# 08-DEV_POWER.net
KiCad netlist of a schematic drawn in Altium Designer
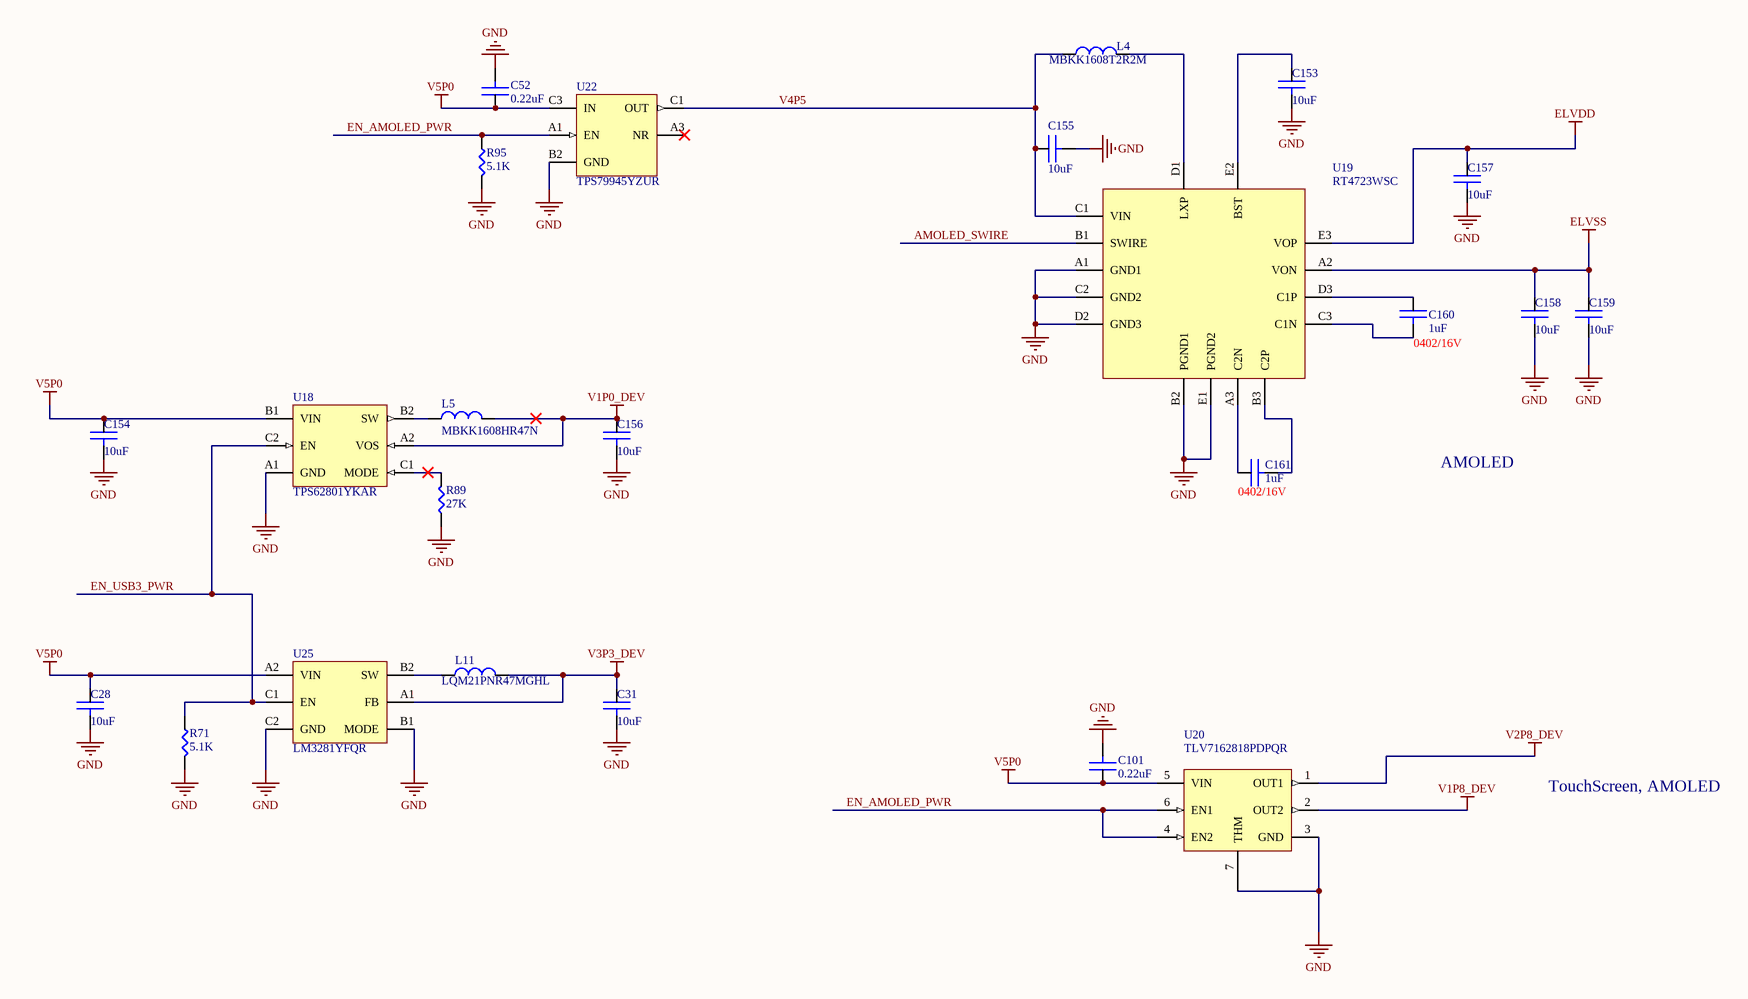
[diagram p0: 08-DEV_POWER.SchDoc]

(export (version "E")
  (design (tool "Eeschema 10.0.6"))
  (components
    (comp (ref "C28") (value "10uF") (footprint "C0402") (libsource (lib "AMOLED") (part "10uF/0402")))
    (comp (ref "C31") (value "10uF") (footprint "C0402") (libsource (lib "AMOLED") (part "10uF/0402")))
    (comp (ref "C52") (value "0.22uF") (footprint "C0201") (libsource (lib "AMOLED") (part "0.22uF/0201")))
    (comp (ref "C101") (value "0.22uF") (footprint "C0201") (libsource (lib "AMOLED") (part "0.22uF/0201")))
    (comp (ref "C153") (value "10uF") (footprint "C0402") (libsource (lib "AMOLED") (part "10uF/0402")))
    (comp (ref "C154") (value "10uF") (footprint "C0402") (libsource (lib "AMOLED") (part "10uF/0402")))
    (comp (ref "C155") (value "10uF") (footprint "C0402") (libsource (lib "AMOLED") (part "10uF/0402")))
    (comp (ref "C156") (value "10uF") (footprint "C0402") (libsource (lib "AMOLED") (part "10uF/0402")))
    (comp (ref "C157") (value "10uF") (footprint "C0402") (libsource (lib "AMOLED") (part "10uF/0402")))
    (comp (ref "C158") (value "10uF") (footprint "C0402") (libsource (lib "AMOLED") (part "10uF/0402")))
    (comp (ref "C159") (value "10uF") (footprint "C0402") (libsource (lib "AMOLED") (part "10uF/0402")))
    (comp (ref "C160") (value "1uF") (footprint "C0402") (libsource (lib "AMOLED") (part "1uF/0402/16V")))
    (comp (ref "C161") (value "1uF") (footprint "C0402") (libsource (lib "AMOLED") (part "1uF/0402/16V")))
    (comp (ref "L4")
      (value "MBKK1608T2R2M")
      (footprint "L0603")
      (libsource (lib "AMOLED") (part "2.2uH/MBKK1608T2R2M"))
    )
    (comp (ref "L5")
      (value "MBKK1608HR47N")
      (footprint "L0603")
      (libsource (lib "AMOLED") (part "0.47uH/MBKK1608HR47N"))
    )
    (comp (ref "L11")
      (value "LQM21PNR47MGHL")
      (footprint "L0805")
      (libsource (lib "AMOLED") (part "0.47uH/LQM21PNR47MGHL"))
    )
    (comp (ref "R71")
      (value "5.1K")
      (footprint "R0201")
      (libsource (lib "Control_Board") (part "5.1K/1%/0201"))
    )
    (comp (ref "R89")
      (value "27K")
      (footprint "R0201")
      (libsource (lib "Control_Board") (part "27K/1%/0201"))
    )
    (comp (ref "R95")
      (value "5.1K")
      (footprint "R0201")
      (libsource (lib "Control_Board") (part "5.1K/1%/0201"))
    )
    (comp (ref "U18")
      (value "TPS62801YKAR")
      (footprint "DSBGA6")
      (description "IC REG BCK 0.85-1.5V 1.0A")
      (libsource (lib "PSD_V2_Schlib") (part "TPS62801YKAR"))
    )
    (comp (ref "U19")
      (value "RT4723WSC")
      (footprint "WLCSP-15B")
      (libsource (lib "AMOLED") (part "RT4723WSC"))
    )
    (comp (ref "U20")
      (value "TLV7162818PDPQR")
      (footprint "X2SON-6")
      (description "Dual LDO 1.8V, 2.8V X2SON-6")
      (libsource (lib "PSD_V2_Schlib") (part "TLV7162818PDPQR"))
    )
    (comp (ref "U22")
      (value "TPS79945YZUR")
      (footprint "DSBGA5")
      (description "LDO 200mA DSBGA")
      (libsource (lib "PSD_V2_Schlib") (part "TPS79945YZUR"))
    )
    (comp (ref "U25")
      (value "LM3281YFQR")
      (footprint "DSBGA6")
      (libsource (lib "AMOLED") (part "LM3281YFQR"))
    )
  )
  (nets
    (net (code "1") (name "/AMOLED_SWIRE") (class "Default")
      (node (ref "U19") (pin "B1") (pinfunction "SWIRE_B1") (pintype "passive"))
    )
    (net (code "2") (name "/EN_AMOLED_PWR") (class "Default")
      (node (ref "R95") (pin "1") (pinfunction "1_1") (pintype "passive"))
      (node (ref "U20") (pin "4") (pinfunction "EN2_4") (pintype "input"))
      (node (ref "U20") (pin "6") (pinfunction "EN1_6") (pintype "input"))
      (node (ref "U22") (pin "A1") (pinfunction "EN_A1") (pintype "input"))
    )
    (net (code "3") (name "/EN_USB3_PWR") (class "Default")
      (node (ref "R71") (pin "1") (pinfunction "1_1") (pintype "passive"))
      (node (ref "U18") (pin "C2") (pinfunction "EN_C2") (pintype "input"))
      (node (ref "U25") (pin "C1") (pinfunction "EN_C1") (pintype "passive"))
    )
    (net (code "4") (name "/V4P5") (class "Default")
      (node (ref "C155") (pin "1") (pinfunction "1_1") (pintype "passive"))
      (node (ref "L4") (pin "1") (pinfunction "1_1") (pintype "passive"))
      (node (ref "U19") (pin "C1") (pinfunction "VIN_C1") (pintype "passive"))
      (node (ref "U22") (pin "C1") (pinfunction "OUT_C1") (pintype "output"))
    )
    (net (code "5") (name "ELVDD") (class "Default")
      (node (ref "C157") (pin "1") (pinfunction "1_1") (pintype "passive"))
      (node (ref "U19") (pin "E3") (pinfunction "VOP_E3") (pintype "passive"))
    )
    (net (code "6") (name "ELVSS") (class "Default")
      (node (ref "C158") (pin "1") (pinfunction "1_1") (pintype "passive"))
      (node (ref "C159") (pin "1") (pinfunction "1_1") (pintype "passive"))
      (node (ref "U19") (pin "A2") (pinfunction "VON_A2") (pintype "passive"))
    )
    (net (code "7") (name "GND") (class "Default")
      (node (ref "C101") (pin "2") (pinfunction "2_2") (pintype "passive"))
      (node (ref "C153") (pin "2") (pinfunction "2_2") (pintype "passive"))
      (node (ref "C154") (pin "2") (pinfunction "2_2") (pintype "passive"))
      (node (ref "C155") (pin "2") (pinfunction "2_2") (pintype "passive"))
      (node (ref "C156") (pin "2") (pinfunction "2_2") (pintype "passive"))
      (node (ref "C157") (pin "2") (pinfunction "2_2") (pintype "passive"))
      (node (ref "C158") (pin "2") (pinfunction "2_2") (pintype "passive"))
      (node (ref "C159") (pin "2") (pinfunction "2_2") (pintype "passive"))
      (node (ref "C28") (pin "2") (pinfunction "2_2") (pintype "passive"))
      (node (ref "C31") (pin "2") (pinfunction "2_2") (pintype "passive"))
      (node (ref "C52") (pin "2") (pinfunction "2_2") (pintype "passive"))
      (node (ref "R71") (pin "2") (pinfunction "2_2") (pintype "passive"))
      (node (ref "R89") (pin "1") (pinfunction "1_1") (pintype "passive"))
      (node (ref "R95") (pin "2") (pinfunction "2_2") (pintype "passive"))
      (node (ref "U18") (pin "A1") (pinfunction "GND_A1") (pintype "power_in"))
      (node (ref "U19") (pin "A1") (pinfunction "GND1_A1") (pintype "passive"))
      (node (ref "U19") (pin "B2") (pinfunction "PGND1_B2") (pintype "passive"))
      (node (ref "U19") (pin "C2") (pinfunction "GND2_C2") (pintype "passive"))
      (node (ref "U19") (pin "D2") (pinfunction "GND3_D2") (pintype "passive"))
      (node (ref "U19") (pin "E1") (pinfunction "PGND2_E1") (pintype "passive"))
      (node (ref "U20") (pin "3") (pinfunction "GND_3") (pintype "passive"))
      (node (ref "U20") (pin "7") (pinfunction "THM_7") (pintype "passive"))
      (node (ref "U22") (pin "B2") (pinfunction "GND_B2") (pintype "power_in"))
      (node (ref "U25") (pin "B1") (pinfunction "MODE_B1") (pintype "passive"))
      (node (ref "U25") (pin "C2") (pinfunction "GND_C2") (pintype "passive"))
    )
    (net (code "8") (name "Net-(U18-MODE)") (class "Default")
      (node (ref "R89") (pin "2") (pinfunction "2_2") (pintype "passive"))
      (node (ref "U18") (pin "C1") (pinfunction "MODE_C1") (pintype "input"))
    )
    (net (code "9") (name "Net-(U18-SW)") (class "Default")
      (node (ref "L5") (pin "1") (pinfunction "1_1") (pintype "passive"))
      (node (ref "U18") (pin "B2") (pinfunction "SW_B2") (pintype "output"))
    )
    (net (code "10") (name "Net-(U19-BST)") (class "Default")
      (node (ref "C153") (pin "1") (pinfunction "1_1") (pintype "passive"))
      (node (ref "U19") (pin "E2") (pinfunction "BST_E2") (pintype "passive"))
    )
    (net (code "11") (name "Net-(U19-C1N)") (class "Default")
      (node (ref "C160") (pin "2") (pinfunction "2_2") (pintype "passive"))
      (node (ref "U19") (pin "C3") (pinfunction "C1N_C3") (pintype "passive"))
    )
    (net (code "12") (name "Net-(U19-C1P)") (class "Default")
      (node (ref "C160") (pin "1") (pinfunction "1_1") (pintype "passive"))
      (node (ref "U19") (pin "D3") (pinfunction "C1P_D3") (pintype "passive"))
    )
    (net (code "13") (name "Net-(U19-C2N)") (class "Default")
      (node (ref "C161") (pin "1") (pinfunction "1_1") (pintype "passive"))
      (node (ref "U19") (pin "A3") (pinfunction "C2N_A3") (pintype "passive"))
    )
    (net (code "14") (name "Net-(U19-C2P)") (class "Default")
      (node (ref "C161") (pin "2") (pinfunction "2_2") (pintype "passive"))
      (node (ref "U19") (pin "B3") (pinfunction "C2P_B3") (pintype "passive"))
    )
    (net (code "15") (name "Net-(U19-LXP)") (class "Default")
      (node (ref "L4") (pin "2") (pinfunction "2_2") (pintype "passive"))
      (node (ref "U19") (pin "D1") (pinfunction "LXP_D1") (pintype "passive"))
    )
    (net (code "16") (name "Net-(U25-SW)") (class "Default")
      (node (ref "L11") (pin "1") (pinfunction "1_1") (pintype "passive"))
      (node (ref "U25") (pin "B2") (pinfunction "SW_B2") (pintype "passive"))
    )
    (net (code "17") (name "V1P0_DEV") (class "Default")
      (node (ref "C156") (pin "1") (pinfunction "1_1") (pintype "passive"))
      (node (ref "L5") (pin "2") (pinfunction "2_2") (pintype "passive"))
      (node (ref "U18") (pin "A2") (pinfunction "VOS_A2") (pintype "input"))
    )
    (net (code "18") (name "V1P8_DEV") (class "Default")
      (node (ref "U20") (pin "2") (pinfunction "OUT2_2") (pintype "output"))
    )
    (net (code "19") (name "V2P8_DEV") (class "Default")
      (node (ref "U20") (pin "1") (pinfunction "OUT1_1") (pintype "output"))
    )
    (net (code "20") (name "V3P3_DEV") (class "Default")
      (node (ref "C31") (pin "1") (pinfunction "1_1") (pintype "passive"))
      (node (ref "L11") (pin "2") (pinfunction "2_2") (pintype "passive"))
      (node (ref "U25") (pin "A1") (pinfunction "FB_A1") (pintype "passive"))
    )
    (net (code "21") (name "V5P0") (class "Default")
      (node (ref "C101") (pin "1") (pinfunction "1_1") (pintype "passive"))
      (node (ref "C154") (pin "1") (pinfunction "1_1") (pintype "passive"))
      (node (ref "C28") (pin "1") (pinfunction "1_1") (pintype "passive"))
      (node (ref "C52") (pin "1") (pinfunction "1_1") (pintype "passive"))
      (node (ref "U18") (pin "B1") (pinfunction "VIN_B1") (pintype "power_in"))
      (node (ref "U20") (pin "5") (pinfunction "VIN_5") (pintype "power_in"))
      (node (ref "U22") (pin "C3") (pinfunction "IN_C3") (pintype "power_in"))
      (node (ref "U25") (pin "A2") (pinfunction "VIN_A2") (pintype "passive"))
    )
    (net (code "22") (name "unconnected-(U22-NR-PadA3)") (class "Default")
      (node (ref "U22") (pin "A3") (pinfunction "NR_A3") (pintype "passive+no_connect"))
    )
  )
)
